# TeensyROM.net
KiCad netlist of a schematic drawn in EAGLE
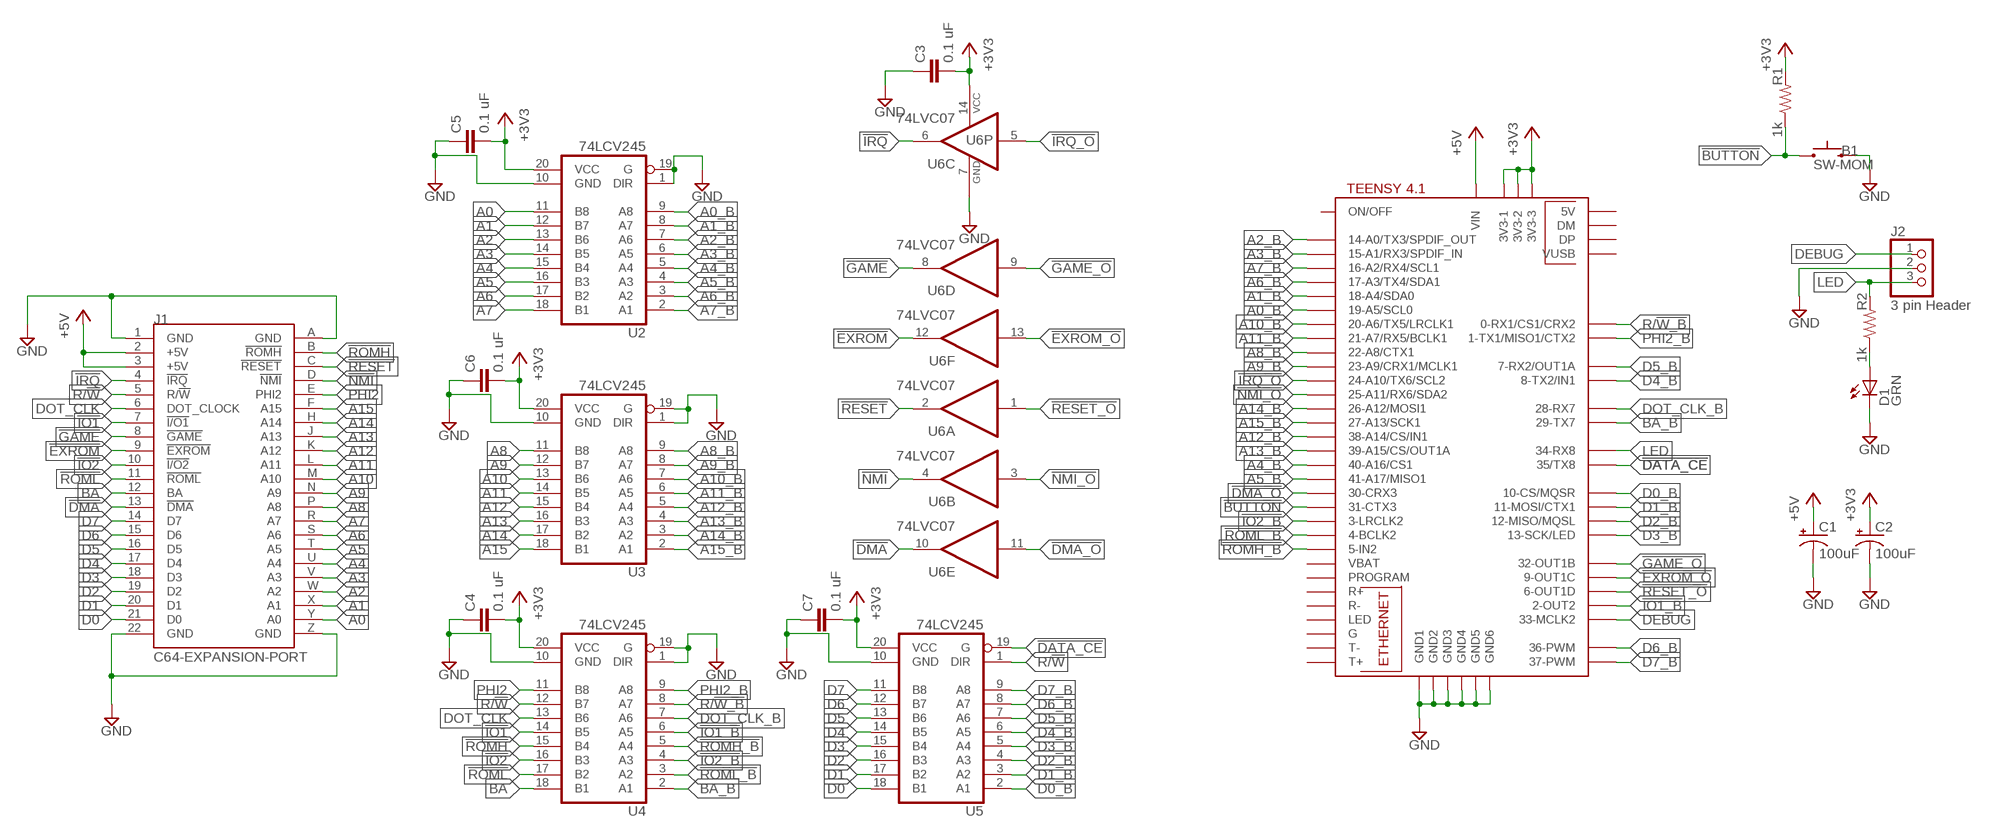
[diagram p0: schematic, sheet 1]

(export (version "E")
  (design (tool "Eeschema 10.0.6"))
  (components
    (comp (ref "B1")
      (value "SW-MOM")
      (footprint "eagle-import:TACTILE-PTH")
      (libsource (lib "eagle-import") (part "SWITCH-MOMENTARY-2PTH"))
    )
    (comp (ref "C1")
      (value "100uF")
      (footprint "eagle-import:E2,5-6")
      (libsource (lib "eagle-import") (part "CPOL-USE2.5-6"))
    )
    (comp (ref "C2")
      (value "100uF")
      (footprint "eagle-import:E2,5-6")
      (libsource (lib "eagle-import") (part "CPOL-USE2.5-6"))
    )
    (comp (ref "C3")
      (value "0.1 uF")
      (footprint "eagle-import:0805")
      (libsource (lib "eagle-import") (part "CAP-0805-0.1UF-50V"))
    )
    (comp (ref "C4")
      (value "0.1 uF")
      (footprint "eagle-import:0805")
      (libsource (lib "eagle-import") (part "CAP-0805-0.1UF-50V"))
    )
    (comp (ref "C5")
      (value "0.1 uF")
      (footprint "eagle-import:0805")
      (libsource (lib "eagle-import") (part "CAP-0805-0.1UF-50V"))
    )
    (comp (ref "C6")
      (value "0.1 uF")
      (footprint "eagle-import:0805")
      (libsource (lib "eagle-import") (part "CAP-0805-0.1UF-50V"))
    )
    (comp (ref "C7")
      (value "0.1 uF")
      (footprint "eagle-import:0805")
      (libsource (lib "eagle-import") (part "CAP-0805-0.1UF-50V"))
    )
    (comp (ref "D1")
      (value "GRN")
      (footprint "eagle-import:LED-3MM-PTH")
      (libsource (lib "eagle-import") (part "LED-3MM-GRN"))
    )
    (comp (ref "J1")
      (value "C64-EXPANSION-PORT")
      (footprint "eagle-import:EXPANSIO_SQ")
      (libsource (lib "eagle-import") (part "C64-EXPANSIONPNARROW"))
    )
    (comp (ref "J2")
      (value "3 pin Header")
      (footprint "eagle-import:1X03")
      (libsource (lib "eagle-import") (part "PINHD-1X3"))
    )
    (comp (ref "R1")
      (value "1k")
      (footprint "eagle-import:R0805")
      (libsource (lib "eagle-import") (part "R-US_R0805"))
    )
    (comp (ref "R2")
      (value "1k")
      (footprint "eagle-import:R0805")
      (libsource (lib "eagle-import") (part "R-US_R0805"))
    )
    (comp (ref "U1")
      (value "TEENSY41")
      (footprint "eagle-import:TEENSY41")
      (libsource (lib "eagle-import") (part "TEENSY41"))
    )
    (comp (ref "U2")
      (value "74LCV245")
      (footprint "eagle-import:SO20W")
      (libsource (lib "eagle-import") (part "74245DWLS"))
    )
    (comp (ref "U3")
      (value "74LCV245")
      (footprint "eagle-import:SO20W")
      (libsource (lib "eagle-import") (part "74245DWLS"))
    )
    (comp (ref "U4")
      (value "74LCV245")
      (footprint "eagle-import:SO20W")
      (libsource (lib "eagle-import") (part "74245DWLS"))
    )
    (comp (ref "U5")
      (value "74LCV245")
      (footprint "eagle-import:SO20W")
      (libsource (lib "eagle-import") (part "74245DWLS"))
    )
    (comp (ref "U6")
      (value "74LVC07")
      (footprint "eagle-import:SO14")
      (libsource (lib "eagle-import") (part "7407DLS"))
    )
  )
  (nets
    (net (code "1") (name "+3V3") (class "Default")
      (node (ref "C2") (pin "+") (pinfunction "+_+") (pintype "passive"))
      (node (ref "C3") (pin "2") (pinfunction "2_2") (pintype "passive"))
      (node (ref "C4") (pin "2") (pinfunction "2_2") (pintype "passive"))
      (node (ref "C5") (pin "2") (pinfunction "2_2") (pintype "passive"))
      (node (ref "C6") (pin "2") (pinfunction "2_2") (pintype "passive"))
      (node (ref "C7") (pin "2") (pinfunction "2_2") (pintype "passive"))
      (node (ref "R1") (pin "2") (pinfunction "2_2") (pintype "passive"))
      (node (ref "U1") (pin "3V3-1") (pinfunction "3V3-1_3V3-1") (pintype "bidirectional"))
      (node (ref "U1") (pin "3V3-2") (pinfunction "3V3-2_3V3-2") (pintype "bidirectional"))
      (node (ref "U1") (pin "3V3-3") (pinfunction "3V3-3_3V3-3") (pintype "bidirectional"))
      (node (ref "U2") (pin "20") (pinfunction "VCC_20") (pintype "bidirectional"))
      (node (ref "U3") (pin "20") (pinfunction "VCC_20") (pintype "bidirectional"))
      (node (ref "U4") (pin "20") (pinfunction "VCC_20") (pintype "bidirectional"))
      (node (ref "U5") (pin "20") (pinfunction "VCC_20") (pintype "bidirectional"))
      (node (ref "U6") (pin "14") (pinfunction "VCC_14") (pintype "power_in"))
    )
    (net (code "2") (name "+5V") (class "Default")
      (node (ref "C1") (pin "+") (pinfunction "+_+") (pintype "passive"))
      (node (ref "J1") (pin "2") (pinfunction "+5V_2") (pintype "power_in"))
      (node (ref "J1") (pin "3") (pinfunction "+5V_3") (pintype "power_in"))
      (node (ref "U1") (pin "VIN") (pinfunction "VIN_VIN") (pintype "bidirectional"))
    )
    (net (code "3") (name "/R{slash}~{W_B}") (class "Default")
      (node (ref "U1") (pin "0-RX1/CS1/CRX2") (pinfunction "0-RX1/CS1/CRX2_0-RX1/CS1/CRX2") (pintype "bidirectional"))
      (node (ref "U4") (pin "8") (pinfunction "A7_8") (pintype "bidirectional"))
    )
    (net (code "4") (name "/R{slash}~{W}") (class "Default")
      (node (ref "J1") (pin "5") (pinfunction "R/~{W}_5") (pintype "output"))
      (node (ref "U4") (pin "12") (pinfunction "B7_12") (pintype "bidirectional"))
      (node (ref "U5") (pin "1") (pinfunction "DIR_1") (pintype "input"))
    )
    (net (code "5") (name "/~{BUTTON}") (class "Default")
      (node (ref "B1") (pin "1") (pinfunction "1_1") (pintype "passive"))
      (node (ref "R1") (pin "1") (pinfunction "1_1") (pintype "passive"))
      (node (ref "U1") (pin "31-CTX3") (pinfunction "31-CTX3_31-CTX3") (pintype "bidirectional"))
    )
    (net (code "6") (name "/~{DATA_CE}") (class "Default")
      (node (ref "U1") (pin "35-TX8") (pinfunction "35/TX8_35-TX8") (pintype "bidirectional"))
      (node (ref "U5") (pin "19") (pinfunction "G_19") (pintype "input"))
    )
    (net (code "7") (name "/~{DMA_O}") (class "Default")
      (node (ref "U1") (pin "30-CRX3") (pinfunction "30-CRX3_30-CRX3") (pintype "bidirectional"))
      (node (ref "U6") (pin "11") (pinfunction "I_11") (pintype "input"))
    )
    (net (code "8") (name "/~{DMA}") (class "Default")
      (node (ref "J1") (pin "13") (pinfunction "~{DMA}_13") (pintype "input"))
      (node (ref "U6") (pin "10") (pinfunction "O_10") (pintype "open_collector"))
    )
    (net (code "9") (name "/~{EXROM_O}") (class "Default")
      (node (ref "U1") (pin "9-OUT1C") (pinfunction "9-OUT1C_9-OUT1C") (pintype "bidirectional"))
      (node (ref "U6") (pin "13") (pinfunction "I_13") (pintype "input"))
    )
    (net (code "10") (name "/~{EXROM}") (class "Default")
      (node (ref "J1") (pin "9") (pinfunction "~{EXROM}_9") (pintype "input"))
      (node (ref "U6") (pin "12") (pinfunction "O_12") (pintype "open_collector"))
    )
    (net (code "11") (name "/~{GAME_O}") (class "Default")
      (node (ref "U1") (pin "32-OUT1B") (pinfunction "32-OUT1B_32-OUT1B") (pintype "bidirectional"))
      (node (ref "U6") (pin "9") (pinfunction "I_9") (pintype "input"))
    )
    (net (code "12") (name "/~{GAME}") (class "Default")
      (node (ref "J1") (pin "8") (pinfunction "~{GAME}_8") (pintype "input"))
      (node (ref "U6") (pin "8") (pinfunction "O_8") (pintype "open_collector"))
    )
    (net (code "13") (name "/~{IO1_B}") (class "Default")
      (node (ref "U1") (pin "2-OUT2") (pinfunction "2-OUT2_2-OUT2") (pintype "bidirectional"))
      (node (ref "U4") (pin "6") (pinfunction "A5_6") (pintype "bidirectional"))
    )
    (net (code "14") (name "/~{IO1}") (class "Default")
      (node (ref "J1") (pin "7") (pinfunction "~{I/O1}_7") (pintype "output"))
      (node (ref "U4") (pin "14") (pinfunction "B5_14") (pintype "bidirectional"))
    )
    (net (code "15") (name "/~{IO2_B}") (class "Default")
      (node (ref "U1") (pin "3-LRCLK2") (pinfunction "3-LRCLK2_3-LRCLK2") (pintype "bidirectional"))
      (node (ref "U4") (pin "4") (pinfunction "A3_4") (pintype "bidirectional"))
    )
    (net (code "16") (name "/~{IO2}") (class "Default")
      (node (ref "J1") (pin "10") (pinfunction "~{I/O2}_10") (pintype "output"))
      (node (ref "U4") (pin "16") (pinfunction "B3_16") (pintype "bidirectional"))
    )
    (net (code "17") (name "/~{IRQ_O}") (class "Default")
      (node (ref "U1") (pin "24-A10/TX6/SCL2") (pinfunction "24-A10/TX6/SCL2_24-A10/TX6/SCL2") (pintype "bidirectional"))
      (node (ref "U6") (pin "5") (pinfunction "I_5") (pintype "input"))
    )
    (net (code "18") (name "/~{IRQ}") (class "Default")
      (node (ref "J1") (pin "4") (pinfunction "~{IRQ}_4") (pintype "input"))
      (node (ref "U6") (pin "6") (pinfunction "O_6") (pintype "open_collector"))
    )
    (net (code "19") (name "/~{NMI_O}") (class "Default")
      (node (ref "U1") (pin "25-A11/RX6/SDA2") (pinfunction "25-A11/RX6/SDA2_25-A11/RX6/SDA2") (pintype "bidirectional"))
      (node (ref "U6") (pin "3") (pinfunction "I_3") (pintype "input"))
    )
    (net (code "20") (name "/~{NMI}") (class "Default")
      (node (ref "J1") (pin "D") (pinfunction "~{NMI}_D") (pintype "input"))
      (node (ref "U6") (pin "4") (pinfunction "O_4") (pintype "open_collector"))
    )
    (net (code "21") (name "/~{RESET_O}") (class "Default")
      (node (ref "U1") (pin "6-OUT1D") (pinfunction "6-OUT1D_6-OUT1D") (pintype "bidirectional"))
      (node (ref "U6") (pin "1") (pinfunction "I_1") (pintype "input"))
    )
    (net (code "22") (name "/~{RESET}") (class "Default")
      (node (ref "J1") (pin "C") (pinfunction "~{RESET}_C") (pintype "open_collector"))
      (node (ref "U6") (pin "2") (pinfunction "O_2") (pintype "open_collector"))
    )
    (net (code "23") (name "/~{ROMH_B}") (class "Default")
      (node (ref "U1") (pin "5-IN2") (pinfunction "5-IN2_5-IN2") (pintype "bidirectional"))
      (node (ref "U4") (pin "5") (pinfunction "A4_5") (pintype "bidirectional"))
    )
    (net (code "24") (name "/~{ROMH}") (class "Default")
      (node (ref "J1") (pin "B") (pinfunction "~{ROMH}_B") (pintype "output"))
      (node (ref "U4") (pin "15") (pinfunction "B4_15") (pintype "bidirectional"))
    )
    (net (code "25") (name "/~{ROML_B}") (class "Default")
      (node (ref "U1") (pin "4-BCLK2") (pinfunction "4-BCLK2_4-BCLK2") (pintype "bidirectional"))
      (node (ref "U4") (pin "3") (pinfunction "A2_3") (pintype "bidirectional"))
    )
    (net (code "26") (name "/~{ROML}") (class "Default")
      (node (ref "J1") (pin "11") (pinfunction "~{ROML}_11") (pintype "output"))
      (node (ref "U4") (pin "17") (pinfunction "B2_17") (pintype "bidirectional"))
    )
    (net (code "27") (name "A0") (class "Default")
      (node (ref "J1") (pin "Y") (pinfunction "A0_Y") (pintype "bidirectional"))
      (node (ref "U2") (pin "11") (pinfunction "B8_11") (pintype "bidirectional"))
    )
    (net (code "28") (name "A0_B") (class "Default")
      (node (ref "U1") (pin "19-A5/SCL0") (pinfunction "19-A5/SCL0_19-A5/SCL0") (pintype "bidirectional"))
      (node (ref "U2") (pin "9") (pinfunction "A8_9") (pintype "bidirectional"))
    )
    (net (code "29") (name "A1") (class "Default")
      (node (ref "J1") (pin "X") (pinfunction "A1_X") (pintype "bidirectional"))
      (node (ref "U2") (pin "12") (pinfunction "B7_12") (pintype "bidirectional"))
    )
    (net (code "30") (name "A1_B") (class "Default")
      (node (ref "U1") (pin "18-A4/SDA0") (pinfunction "18-A4/SDA0_18-A4/SDA0") (pintype "bidirectional"))
      (node (ref "U2") (pin "8") (pinfunction "A7_8") (pintype "bidirectional"))
    )
    (net (code "31") (name "A2") (class "Default")
      (node (ref "J1") (pin "W") (pinfunction "A2_W") (pintype "bidirectional"))
      (node (ref "U2") (pin "13") (pinfunction "B6_13") (pintype "bidirectional"))
    )
    (net (code "32") (name "A2_B") (class "Default")
      (node (ref "U1") (pin "14-A0/TX3/SPDIF_OUT") (pinfunction "14-A0/TX3/SPDIF_OUT_14-A0/TX3/SPDIF_OUT") (pintype "bidirectional"))
      (node (ref "U2") (pin "7") (pinfunction "A6_7") (pintype "bidirectional"))
    )
    (net (code "33") (name "A3") (class "Default")
      (node (ref "J1") (pin "V") (pinfunction "A3_V") (pintype "bidirectional"))
      (node (ref "U2") (pin "14") (pinfunction "B5_14") (pintype "bidirectional"))
    )
    (net (code "34") (name "A3_B") (class "Default")
      (node (ref "U1") (pin "15-A1/RX3/SPDIF_IN") (pinfunction "15-A1/RX3/SPDIF_IN_15-A1/RX3/SPDIF_IN") (pintype "bidirectional"))
      (node (ref "U2") (pin "6") (pinfunction "A5_6") (pintype "bidirectional"))
    )
    (net (code "35") (name "A4") (class "Default")
      (node (ref "J1") (pin "U") (pinfunction "A4_U") (pintype "bidirectional"))
      (node (ref "U2") (pin "15") (pinfunction "B4_15") (pintype "bidirectional"))
    )
    (net (code "36") (name "A4_B") (class "Default")
      (node (ref "U1") (pin "40-A16/CS1") (pinfunction "40-A16/CS1_40-A16/CS1") (pintype "bidirectional"))
      (node (ref "U2") (pin "5") (pinfunction "A4_5") (pintype "bidirectional"))
    )
    (net (code "37") (name "A5") (class "Default")
      (node (ref "J1") (pin "T") (pinfunction "A5_T") (pintype "bidirectional"))
      (node (ref "U2") (pin "16") (pinfunction "B3_16") (pintype "bidirectional"))
    )
    (net (code "38") (name "A5_B") (class "Default")
      (node (ref "U1") (pin "41-A17/MISO1") (pinfunction "41-A17/MISO1_41-A17/MISO1") (pintype "bidirectional"))
      (node (ref "U2") (pin "4") (pinfunction "A3_4") (pintype "bidirectional"))
    )
    (net (code "39") (name "A6") (class "Default")
      (node (ref "J1") (pin "S") (pinfunction "A6_S") (pintype "bidirectional"))
      (node (ref "U2") (pin "17") (pinfunction "B2_17") (pintype "bidirectional"))
    )
    (net (code "40") (name "A6_B") (class "Default")
      (node (ref "U1") (pin "17-A3/TX4/SDA1") (pinfunction "17-A3/TX4/SDA1_17-A3/TX4/SDA1") (pintype "bidirectional"))
      (node (ref "U2") (pin "3") (pinfunction "A2_3") (pintype "bidirectional"))
    )
    (net (code "41") (name "A7") (class "Default")
      (node (ref "J1") (pin "R") (pinfunction "A7_R") (pintype "bidirectional"))
      (node (ref "U2") (pin "18") (pinfunction "B1_18") (pintype "bidirectional"))
    )
    (net (code "42") (name "A7_B") (class "Default")
      (node (ref "U1") (pin "16-A2/RX4/SCL1") (pinfunction "16-A2/RX4/SCL1_16-A2/RX4/SCL1") (pintype "bidirectional"))
      (node (ref "U2") (pin "2") (pinfunction "A1_2") (pintype "bidirectional"))
    )
    (net (code "43") (name "A8") (class "Default")
      (node (ref "J1") (pin "P") (pinfunction "A8_P") (pintype "bidirectional"))
      (node (ref "U3") (pin "11") (pinfunction "B8_11") (pintype "bidirectional"))
    )
    (net (code "44") (name "A8_B") (class "Default")
      (node (ref "U1") (pin "22-A8/CTX1") (pinfunction "22-A8/CTX1_22-A8/CTX1") (pintype "bidirectional"))
      (node (ref "U3") (pin "9") (pinfunction "A8_9") (pintype "bidirectional"))
    )
    (net (code "45") (name "A9") (class "Default")
      (node (ref "J1") (pin "N") (pinfunction "A9_N") (pintype "bidirectional"))
      (node (ref "U3") (pin "12") (pinfunction "B7_12") (pintype "bidirectional"))
    )
    (net (code "46") (name "A9_B") (class "Default")
      (node (ref "U1") (pin "23-A9/CRX1/MCLK1") (pinfunction "23-A9/CRX1/MCLK1_23-A9/CRX1/MCLK1") (pintype "bidirectional"))
      (node (ref "U3") (pin "8") (pinfunction "A7_8") (pintype "bidirectional"))
    )
    (net (code "47") (name "A10") (class "Default")
      (node (ref "J1") (pin "M") (pinfunction "A10_M") (pintype "bidirectional"))
      (node (ref "U3") (pin "13") (pinfunction "B6_13") (pintype "bidirectional"))
    )
    (net (code "48") (name "A10_B") (class "Default")
      (node (ref "U1") (pin "20-A6/TX5/LRCLK1") (pinfunction "20-A6/TX5/LRCLK1_20-A6/TX5/LRCLK1") (pintype "bidirectional"))
      (node (ref "U3") (pin "7") (pinfunction "A6_7") (pintype "bidirectional"))
    )
    (net (code "49") (name "A11") (class "Default")
      (node (ref "J1") (pin "L") (pinfunction "A11_L") (pintype "bidirectional"))
      (node (ref "U3") (pin "14") (pinfunction "B5_14") (pintype "bidirectional"))
    )
    (net (code "50") (name "A11_B") (class "Default")
      (node (ref "U1") (pin "21-A7/RX5/BCLK1") (pinfunction "21-A7/RX5/BCLK1_21-A7/RX5/BCLK1") (pintype "bidirectional"))
      (node (ref "U3") (pin "6") (pinfunction "A5_6") (pintype "bidirectional"))
    )
    (net (code "51") (name "A12") (class "Default")
      (node (ref "J1") (pin "K") (pinfunction "A12_K") (pintype "bidirectional"))
      (node (ref "U3") (pin "15") (pinfunction "B4_15") (pintype "bidirectional"))
    )
    (net (code "52") (name "A12_B") (class "Default")
      (node (ref "U1") (pin "38-A14/CS/IN1") (pinfunction "38-A14/CS/IN1_38-A14/CS/IN1") (pintype "bidirectional"))
      (node (ref "U3") (pin "5") (pinfunction "A4_5") (pintype "bidirectional"))
    )
    (net (code "53") (name "A13") (class "Default")
      (node (ref "J1") (pin "J") (pinfunction "A13_J") (pintype "bidirectional"))
      (node (ref "U3") (pin "16") (pinfunction "B3_16") (pintype "bidirectional"))
    )
    (net (code "54") (name "A13_B") (class "Default")
      (node (ref "U1") (pin "39-A15/CS/OUT1A") (pinfunction "39-A15/CS/OUT1A_39-A15/CS/OUT1A") (pintype "bidirectional"))
      (node (ref "U3") (pin "4") (pinfunction "A3_4") (pintype "bidirectional"))
    )
    (net (code "55") (name "A14") (class "Default")
      (node (ref "J1") (pin "H") (pinfunction "A14_H") (pintype "bidirectional"))
      (node (ref "U3") (pin "17") (pinfunction "B2_17") (pintype "bidirectional"))
    )
    (net (code "56") (name "A14_B") (class "Default")
      (node (ref "U1") (pin "26-A12/MOSI1") (pinfunction "26-A12/MOSI1_26-A12/MOSI1") (pintype "bidirectional"))
      (node (ref "U3") (pin "3") (pinfunction "A2_3") (pintype "bidirectional"))
    )
    (net (code "57") (name "A15") (class "Default")
      (node (ref "J1") (pin "F") (pinfunction "A15_F") (pintype "bidirectional"))
      (node (ref "U3") (pin "18") (pinfunction "B1_18") (pintype "bidirectional"))
    )
    (net (code "58") (name "A15_B") (class "Default")
      (node (ref "U1") (pin "27-A13/SCK1") (pinfunction "27-A13/SCK1_27-A13/SCK1") (pintype "bidirectional"))
      (node (ref "U3") (pin "2") (pinfunction "A1_2") (pintype "bidirectional"))
    )
    (net (code "59") (name "BA") (class "Default")
      (node (ref "J1") (pin "12") (pinfunction "BA_12") (pintype "output"))
      (node (ref "U4") (pin "18") (pinfunction "B1_18") (pintype "bidirectional"))
    )
    (net (code "60") (name "BA_B") (class "Default")
      (node (ref "U1") (pin "29-TX7") (pinfunction "29-TX7_29-TX7") (pintype "bidirectional"))
      (node (ref "U4") (pin "2") (pinfunction "A1_2") (pintype "bidirectional"))
    )
    (net (code "61") (name "D0") (class "Default")
      (node (ref "J1") (pin "21") (pinfunction "D0_21") (pintype "bidirectional"))
      (node (ref "U5") (pin "18") (pinfunction "B1_18") (pintype "bidirectional"))
    )
    (net (code "62") (name "D0_B") (class "Default")
      (node (ref "U1") (pin "10-CS\\MQSR") (pinfunction "10-CS/MQSR_10-CS\\MQSR") (pintype "bidirectional"))
      (node (ref "U5") (pin "2") (pinfunction "A1_2") (pintype "bidirectional"))
    )
    (net (code "63") (name "D1") (class "Default")
      (node (ref "J1") (pin "20") (pinfunction "D1_20") (pintype "bidirectional"))
      (node (ref "U5") (pin "17") (pinfunction "B2_17") (pintype "bidirectional"))
    )
    (net (code "64") (name "D1_B") (class "Default")
      (node (ref "U1") (pin "11-MOSI/CTX1") (pinfunction "11-MOSI/CTX1_11-MOSI/CTX1") (pintype "bidirectional"))
      (node (ref "U5") (pin "3") (pinfunction "A2_3") (pintype "bidirectional"))
    )
    (net (code "65") (name "D2") (class "Default")
      (node (ref "J1") (pin "19") (pinfunction "D2_19") (pintype "bidirectional"))
      (node (ref "U5") (pin "16") (pinfunction "B3_16") (pintype "bidirectional"))
    )
    (net (code "66") (name "D2_B") (class "Default")
      (node (ref "U1") (pin "12-MISO/MQSL") (pinfunction "12-MISO/MQSL_12-MISO/MQSL") (pintype "bidirectional"))
      (node (ref "U5") (pin "4") (pinfunction "A3_4") (pintype "bidirectional"))
    )
    (net (code "67") (name "D3") (class "Default")
      (node (ref "J1") (pin "18") (pinfunction "D3_18") (pintype "bidirectional"))
      (node (ref "U5") (pin "15") (pinfunction "B4_15") (pintype "bidirectional"))
    )
    (net (code "68") (name "D3_B") (class "Default")
      (node (ref "U1") (pin "13-SCK/LED") (pinfunction "13-SCK/LED_13-SCK/LED") (pintype "bidirectional"))
      (node (ref "U5") (pin "5") (pinfunction "A4_5") (pintype "bidirectional"))
    )
    (net (code "69") (name "D4") (class "Default")
      (node (ref "J1") (pin "17") (pinfunction "D4_17") (pintype "bidirectional"))
      (node (ref "U5") (pin "14") (pinfunction "B5_14") (pintype "bidirectional"))
    )
    (net (code "70") (name "D4_B") (class "Default")
      (node (ref "U1") (pin "8-TX2/IN1") (pinfunction "8-TX2/IN1_8-TX2/IN1") (pintype "bidirectional"))
      (node (ref "U5") (pin "6") (pinfunction "A5_6") (pintype "bidirectional"))
    )
    (net (code "71") (name "D5") (class "Default")
      (node (ref "J1") (pin "16") (pinfunction "D5_16") (pintype "bidirectional"))
      (node (ref "U5") (pin "13") (pinfunction "B6_13") (pintype "bidirectional"))
    )
    (net (code "72") (name "D5_B") (class "Default")
      (node (ref "U1") (pin "7-RX2/OUT1A") (pinfunction "7-RX2/OUT1A_7-RX2/OUT1A") (pintype "bidirectional"))
      (node (ref "U5") (pin "7") (pinfunction "A6_7") (pintype "bidirectional"))
    )
    (net (code "73") (name "D6") (class "Default")
      (node (ref "J1") (pin "15") (pinfunction "D6_15") (pintype "bidirectional"))
      (node (ref "U5") (pin "12") (pinfunction "B7_12") (pintype "bidirectional"))
    )
    (net (code "74") (name "D6_B") (class "Default")
      (node (ref "U1") (pin "36-PWM") (pinfunction "36-PWM_36-PWM") (pintype "bidirectional"))
      (node (ref "U5") (pin "8") (pinfunction "A7_8") (pintype "bidirectional"))
    )
    (net (code "75") (name "D7") (class "Default")
      (node (ref "J1") (pin "14") (pinfunction "D7_14") (pintype "bidirectional"))
      (node (ref "U5") (pin "11") (pinfunction "B8_11") (pintype "bidirectional"))
    )
    (net (code "76") (name "D7_B") (class "Default")
      (node (ref "U1") (pin "37-PWM") (pinfunction "37-PWM_37-PWM") (pintype "bidirectional"))
      (node (ref "U5") (pin "9") (pinfunction "A8_9") (pintype "bidirectional"))
    )
    (net (code "77") (name "DEBUG") (class "Default")
      (node (ref "J2") (pin "1") (pinfunction "1_1") (pintype "passive"))
      (node (ref "U1") (pin "33-MCLK2") (pinfunction "33-MCLK2_33-MCLK2") (pintype "bidirectional"))
    )
    (net (code "78") (name "DOT_CLK") (class "Default")
      (node (ref "J1") (pin "6") (pinfunction "DOT_CLOCK_6") (pintype "output"))
      (node (ref "U4") (pin "13") (pinfunction "B6_13") (pintype "bidirectional"))
    )
    (net (code "79") (name "DOT_CLK_B") (class "Default")
      (node (ref "U1") (pin "28-RX7") (pinfunction "28-RX7_28-RX7") (pintype "bidirectional"))
      (node (ref "U4") (pin "7") (pinfunction "A6_7") (pintype "bidirectional"))
    )
    (net (code "80") (name "GND") (class "Default")
      (node (ref "B1") (pin "3") (pinfunction "2_3") (pintype "passive"))
      (node (ref "C1") (pin "-") (pinfunction "-_-") (pintype "passive"))
      (node (ref "C2") (pin "-") (pinfunction "-_-") (pintype "passive"))
      (node (ref "C3") (pin "1") (pinfunction "1_1") (pintype "passive"))
      (node (ref "C4") (pin "1") (pinfunction "1_1") (pintype "passive"))
      (node (ref "C5") (pin "1") (pinfunction "1_1") (pintype "passive"))
      (node (ref "C6") (pin "1") (pinfunction "1_1") (pintype "passive"))
      (node (ref "C7") (pin "1") (pinfunction "1_1") (pintype "passive"))
      (node (ref "D1") (pin "K") (pinfunction "C_K") (pintype "passive"))
      (node (ref "J1") (pin "1") (pinfunction "GND_1") (pintype "power_in"))
      (node (ref "J1") (pin "22") (pinfunction "GND_22") (pintype "power_in"))
      (node (ref "J1") (pin "A") (pinfunction "GND_A") (pintype "power_in"))
      (node (ref "J1") (pin "Z") (pinfunction "GND_Z") (pintype "power_in"))
      (node (ref "J2") (pin "2") (pinfunction "2_2") (pintype "passive"))
      (node (ref "U1") (pin "GND1") (pinfunction "GND1_GND1") (pintype "bidirectional"))
      (node (ref "U1") (pin "GND2") (pinfunction "GND2_GND2") (pintype "bidirectional"))
      (node (ref "U1") (pin "GND3") (pinfunction "GND3_GND3") (pintype "bidirectional"))
      (node (ref "U1") (pin "GND4") (pinfunction "GND4_GND4") (pintype "bidirectional"))
      (node (ref "U1") (pin "GND5") (pinfunction "GND5_GND5") (pintype "bidirectional"))
      (node (ref "U1") (pin "GND6") (pinfunction "GND6_GND6") (pintype "bidirectional"))
      (node (ref "U2") (pin "1") (pinfunction "DIR_1") (pintype "input"))
      (node (ref "U2") (pin "10") (pinfunction "GND_10") (pintype "bidirectional"))
      (node (ref "U2") (pin "19") (pinfunction "G_19") (pintype "input"))
      (node (ref "U3") (pin "1") (pinfunction "DIR_1") (pintype "input"))
      (node (ref "U3") (pin "10") (pinfunction "GND_10") (pintype "bidirectional"))
      (node (ref "U3") (pin "19") (pinfunction "G_19") (pintype "input"))
      (node (ref "U4") (pin "1") (pinfunction "DIR_1") (pintype "input"))
      (node (ref "U4") (pin "10") (pinfunction "GND_10") (pintype "bidirectional"))
      (node (ref "U4") (pin "19") (pinfunction "G_19") (pintype "input"))
      (node (ref "U5") (pin "10") (pinfunction "GND_10") (pintype "bidirectional"))
      (node (ref "U6") (pin "7") (pinfunction "GND_7") (pintype "power_in"))
    )
    (net (code "81") (name "LED") (class "Default")
      (node (ref "J2") (pin "3") (pinfunction "3_3") (pintype "passive"))
      (node (ref "R2") (pin "2") (pinfunction "2_2") (pintype "passive"))
      (node (ref "U1") (pin "34-RX8") (pinfunction "34-RX8_34-RX8") (pintype "bidirectional"))
    )
    (net (code "82") (name "Net-(D1-PadA)") (class "Default")
      (node (ref "D1") (pin "A") (pinfunction "A_A") (pintype "passive"))
      (node (ref "R2") (pin "1") (pinfunction "1_1") (pintype "passive"))
    )
    (net (code "83") (name "PHI2") (class "Default")
      (node (ref "J1") (pin "E") (pinfunction "PHI2_E") (pintype "output"))
      (node (ref "U4") (pin "11") (pinfunction "B8_11") (pintype "bidirectional"))
    )
    (net (code "84") (name "PHI2_B") (class "Default")
      (node (ref "U1") (pin "1-TX1/MISO1/CTX2") (pinfunction "1-TX1/MISO1/CTX2_1-TX1/MISO1/CTX2") (pintype "bidirectional"))
      (node (ref "U4") (pin "9") (pinfunction "A8_9") (pintype "bidirectional"))
    )
    (net (code "85") (name "unconnected-(U1-5V-Pad+5V)") (class "Default")
      (node (ref "U1") (pin "+5V") (pinfunction "5V_+5V") (pintype "bidirectional"))
    )
    (net (code "86") (name "unconnected-(U1-PadDM)") (class "Default")
      (node (ref "U1") (pin "DM") (pinfunction "DM_DM") (pintype "bidirectional"))
    )
    (net (code "87") (name "unconnected-(U1-PadDP)") (class "Default")
      (node (ref "U1") (pin "DP") (pinfunction "DP_DP") (pintype "bidirectional"))
    )
    (net (code "88") (name "unconnected-(U1-PadG)") (class "Default")
      (node (ref "U1") (pin "G") (pinfunction "G_G") (pintype "bidirectional"))
    )
    (net (code "89") (name "unconnected-(U1-PadLED)") (class "Default")
      (node (ref "U1") (pin "LED") (pinfunction "LED_LED") (pintype "bidirectional"))
    )
    (net (code "90") (name "unconnected-(U1-PadON{slash}OFF)") (class "Default")
      (node (ref "U1") (pin "ON/OFF") (pinfunction "ON/OFF_ON/OFF") (pintype "bidirectional"))
    )
    (net (code "91") (name "unconnected-(U1-PadPROGRAM)") (class "Default")
      (node (ref "U1") (pin "PROGRAM") (pinfunction "PROGRAM_PROGRAM") (pintype "bidirectional"))
    )
    (net (code "92") (name "unconnected-(U1-PadR+)") (class "Default")
      (node (ref "U1") (pin "R+") (pinfunction "R+_R+") (pintype "bidirectional"))
    )
    (net (code "93") (name "unconnected-(U1-PadR-)") (class "Default")
      (node (ref "U1") (pin "R-") (pinfunction "R-_R-") (pintype "bidirectional"))
    )
    (net (code "94") (name "unconnected-(U1-PadT+)") (class "Default")
      (node (ref "U1") (pin "T+") (pinfunction "T+_T+") (pintype "bidirectional"))
    )
    (net (code "95") (name "unconnected-(U1-PadT-)") (class "Default")
      (node (ref "U1") (pin "T-") (pinfunction "T-_T-") (pintype "bidirectional"))
    )
    (net (code "96") (name "unconnected-(U1-PadVBAT)") (class "Default")
      (node (ref "U1") (pin "VBAT") (pinfunction "VBAT_VBAT") (pintype "bidirectional"))
    )
    (net (code "97") (name "unconnected-(U1-PadVUSB)") (class "Default")
      (node (ref "U1") (pin "VUSB") (pinfunction "VUSB_VUSB") (pintype "bidirectional"))
    )
  )
)
